# Board_ESP32_V1.net
KiCad netlist of a schematic drawn in EAGLE
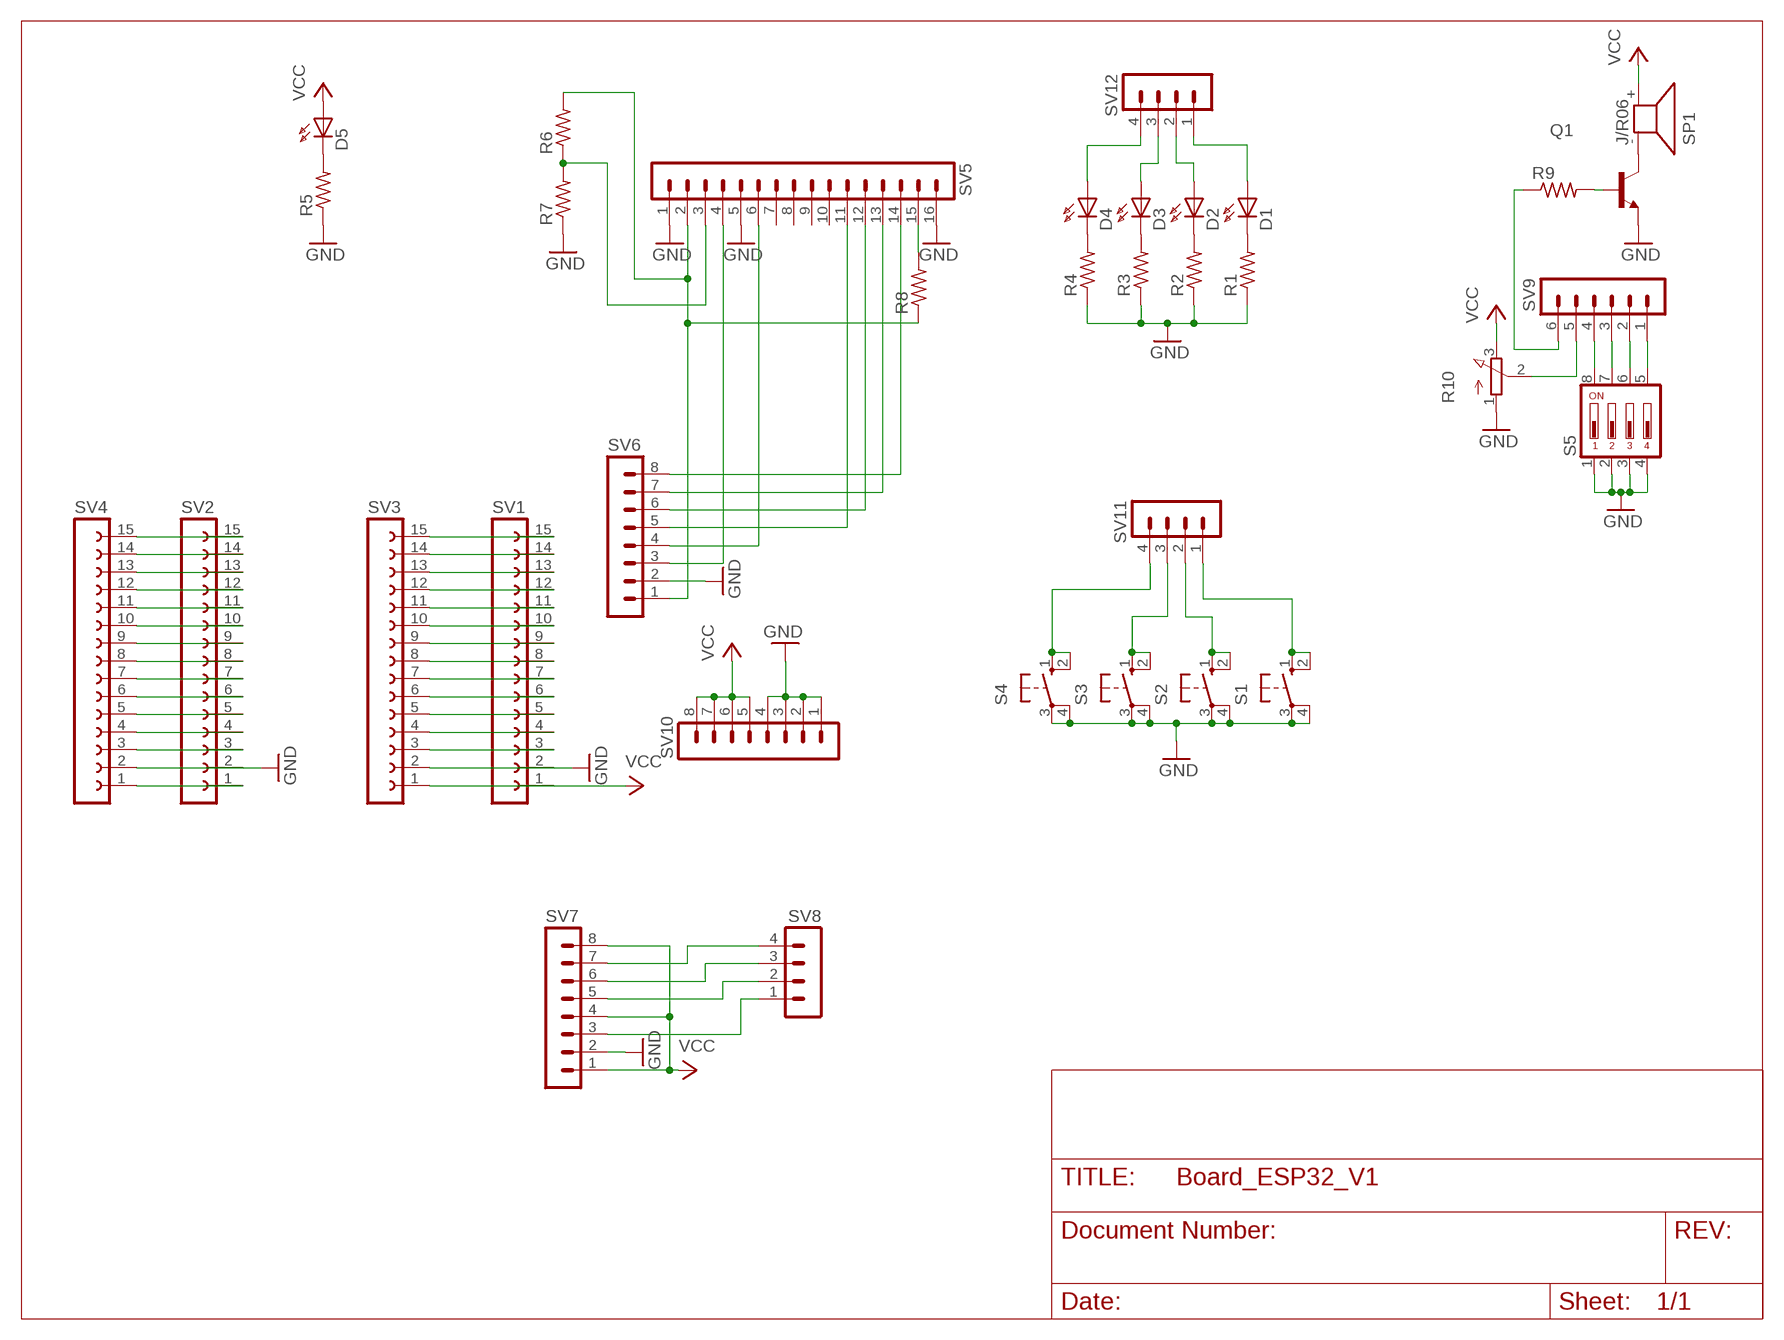
[diagram p0: schematic, sheet 1]

(export (version "E")
  (design (tool "Eeschema 10.0.6"))
  (components
    (comp (ref "D1")
      (value "LED3MM")
      (footprint "eagle-import:LED3MM")
      (libsource (lib "eagle-import") (part "LED3MM"))
    )
    (comp (ref "D2")
      (value "LED3MM")
      (footprint "eagle-import:LED3MM")
      (libsource (lib "eagle-import") (part "LED3MM"))
    )
    (comp (ref "D3")
      (value "LED3MM")
      (footprint "eagle-import:LED3MM")
      (libsource (lib "eagle-import") (part "LED3MM"))
    )
    (comp (ref "D4")
      (value "LED3MM")
      (footprint "eagle-import:LED3MM")
      (libsource (lib "eagle-import") (part "LED3MM"))
    )
    (comp (ref "D5")
      (value "LED3MM")
      (footprint "eagle-import:LED3MM")
      (libsource (lib "eagle-import") (part "LED3MM"))
    )
    (comp (ref "Q1")
      (value "2N3904")
      (footprint "eagle-import:TO92")
      (libsource (lib "eagle-import") (part "2N3904"))
    )
    (comp (ref "R1")
      (value "R-US_0207/10")
      (footprint "eagle-import:0207_10")
      (libsource (lib "eagle-import") (part "R-US_0207/10"))
    )
    (comp (ref "R2")
      (value "R-US_0207/10")
      (footprint "eagle-import:0207_10")
      (libsource (lib "eagle-import") (part "R-US_0207/10"))
    )
    (comp (ref "R3")
      (value "R-US_0207/10")
      (footprint "eagle-import:0207_10")
      (libsource (lib "eagle-import") (part "R-US_0207/10"))
    )
    (comp (ref "R4")
      (value "R-US_0207/10")
      (footprint "eagle-import:0207_10")
      (libsource (lib "eagle-import") (part "R-US_0207/10"))
    )
    (comp (ref "R5")
      (value "R-US_0207/10")
      (footprint "eagle-import:0207_10")
      (libsource (lib "eagle-import") (part "R-US_0207/10"))
    )
    (comp (ref "R6")
      (value "R-US_0207/10")
      (footprint "eagle-import:0207_10")
      (libsource (lib "eagle-import") (part "R-US_0207/10"))
    )
    (comp (ref "R7")
      (value "R-US_0207/10")
      (footprint "eagle-import:0207_10")
      (libsource (lib "eagle-import") (part "R-US_0207/10"))
    )
    (comp (ref "R8")
      (value "R-US_0207/10")
      (footprint "eagle-import:0207_10")
      (libsource (lib "eagle-import") (part "R-US_0207/10"))
    )
    (comp (ref "R9")
      (value "R-US_0207/10")
      (footprint "eagle-import:0207_10")
      (libsource (lib "eagle-import") (part "R-US_0207/10"))
    )
    (comp (ref "R10")
      (value "3RP/1610N")
      (footprint "eagle-import:3RP_1610N")
      (libsource (lib "eagle-import") (part "3RP/1610N"))
    )
    (comp (ref "S1")
      (value "10-XX")
      (footprint "eagle-import:B3F-10XX")
      (fields (field (name "MPN") "B3F-1000"))
      (libsource (lib "eagle-import") (part "10-XX"))
    )
    (comp (ref "S2")
      (value "10-XX")
      (footprint "eagle-import:B3F-10XX")
      (fields (field (name "MPN") "B3F-1000"))
      (libsource (lib "eagle-import") (part "10-XX"))
    )
    (comp (ref "S3")
      (value "10-XX")
      (footprint "eagle-import:B3F-10XX")
      (fields (field (name "MPN") "B3F-1000"))
      (libsource (lib "eagle-import") (part "10-XX"))
    )
    (comp (ref "S4")
      (value "10-XX")
      (footprint "eagle-import:B3F-10XX")
      (fields (field (name "MPN") "B3F-1000"))
      (libsource (lib "eagle-import") (part "10-XX"))
    )
    (comp (ref "S5")
      (value "DIP04YL")
      (footprint "eagle-import:DIP04YL")
      (libsource (lib "eagle-import") (part "DIP04YL"))
    )
    (comp (ref "SP1")
      (value "J/R06")
      (footprint "eagle-import:J_R06")
      (libsource (lib "eagle-import") (part "J/R06"))
    )
    (comp (ref "SV1")
      (value "FE15-1")
      (footprint "eagle-import:FE15")
      (libsource (lib "eagle-import") (part "FE15-1"))
    )
    (comp (ref "SV2")
      (value "FE15-1")
      (footprint "eagle-import:FE15")
      (libsource (lib "eagle-import") (part "FE15-1"))
    )
    (comp (ref "SV3")
      (value "FE15-1")
      (footprint "eagle-import:FE15")
      (libsource (lib "eagle-import") (part "FE15-1"))
    )
    (comp (ref "SV4")
      (value "FE15-1")
      (footprint "eagle-import:FE15")
      (libsource (lib "eagle-import") (part "FE15-1"))
    )
    (comp (ref "SV5")
      (value "MA16-1")
      (footprint "eagle-import:MA16-1")
      (libsource (lib "eagle-import") (part "MA16-1"))
    )
    (comp (ref "SV6")
      (value "MA08-1")
      (footprint "eagle-import:MA08-1")
      (libsource (lib "eagle-import") (part "MA08-1"))
    )
    (comp (ref "SV7")
      (value "MA08-1")
      (footprint "eagle-import:MA08-1")
      (libsource (lib "eagle-import") (part "MA08-1"))
    )
    (comp (ref "SV8")
      (value "MA04-1")
      (footprint "eagle-import:MA04-1")
      (libsource (lib "eagle-import") (part "MA04-1"))
    )
    (comp (ref "SV9")
      (value "MA06-1")
      (footprint "eagle-import:MA06-1")
      (libsource (lib "eagle-import") (part "MA06-1"))
    )
    (comp (ref "SV10")
      (value "MA08-1")
      (footprint "eagle-import:MA08-1")
      (libsource (lib "eagle-import") (part "MA08-1"))
    )
    (comp (ref "SV11")
      (value "MA04-1")
      (footprint "eagle-import:MA04-1")
      (libsource (lib "eagle-import") (part "MA04-1"))
    )
    (comp (ref "SV12")
      (value "MA04-1")
      (footprint "eagle-import:MA04-1")
      (libsource (lib "eagle-import") (part "MA04-1"))
    )
  )
  (nets
    (net (code "1") (name "GND") (class "Default")
      (node (ref "Q1") (pin "3") (pinfunction "E_3") (pintype "passive"))
      (node (ref "R1") (pin "1") (pinfunction "1_1") (pintype "passive"))
      (node (ref "R10") (pin "1") (pinfunction "A_1") (pintype "passive"))
      (node (ref "R2") (pin "1") (pinfunction "1_1") (pintype "passive"))
      (node (ref "R3") (pin "1") (pinfunction "1_1") (pintype "passive"))
      (node (ref "R4") (pin "1") (pinfunction "1_1") (pintype "passive"))
      (node (ref "R5") (pin "1") (pinfunction "1_1") (pintype "passive"))
      (node (ref "R7") (pin "1") (pinfunction "1_1") (pintype "passive"))
      (node (ref "S1") (pin "3") (pinfunction "P_3") (pintype "passive"))
      (node (ref "S1") (pin "4") (pinfunction "P1_4") (pintype "passive"))
      (node (ref "S2") (pin "3") (pinfunction "P_3") (pintype "passive"))
      (node (ref "S2") (pin "4") (pinfunction "P1_4") (pintype "passive"))
      (node (ref "S3") (pin "3") (pinfunction "P_3") (pintype "passive"))
      (node (ref "S3") (pin "4") (pinfunction "P1_4") (pintype "passive"))
      (node (ref "S4") (pin "3") (pinfunction "P_3") (pintype "passive"))
      (node (ref "S4") (pin "4") (pinfunction "P1_4") (pintype "passive"))
      (node (ref "S5") (pin "1") (pinfunction "1_1") (pintype "passive"))
      (node (ref "S5") (pin "2") (pinfunction "2_2") (pintype "passive"))
      (node (ref "S5") (pin "3") (pinfunction "3_3") (pintype "passive"))
      (node (ref "S5") (pin "4") (pinfunction "4_4") (pintype "passive"))
      (node (ref "SV1") (pin "2") (pinfunction "2_2") (pintype "passive"))
      (node (ref "SV10") (pin "1") (pinfunction "1_1") (pintype "passive"))
      (node (ref "SV10") (pin "2") (pinfunction "2_2") (pintype "passive"))
      (node (ref "SV10") (pin "3") (pinfunction "3_3") (pintype "passive"))
      (node (ref "SV10") (pin "4") (pinfunction "4_4") (pintype "passive"))
      (node (ref "SV2") (pin "2") (pinfunction "2_2") (pintype "passive"))
      (node (ref "SV3") (pin "2") (pinfunction "2_2") (pintype "passive"))
      (node (ref "SV4") (pin "2") (pinfunction "2_2") (pintype "passive"))
      (node (ref "SV5") (pin "1") (pinfunction "1_1") (pintype "passive"))
      (node (ref "SV5") (pin "16") (pinfunction "16_16") (pintype "passive"))
      (node (ref "SV5") (pin "5") (pinfunction "5_5") (pintype "passive"))
      (node (ref "SV6") (pin "2") (pinfunction "2_2") (pintype "passive"))
      (node (ref "SV7") (pin "2") (pinfunction "2_2") (pintype "passive"))
    )
    (net (code "2") (name "Net-(D1-C)") (class "Default")
      (node (ref "D1") (pin "K") (pinfunction "C_K") (pintype "passive"))
      (node (ref "R1") (pin "2") (pinfunction "2_2") (pintype "passive"))
    )
    (net (code "3") (name "Net-(D1-PadA)") (class "Default")
      (node (ref "D1") (pin "A") (pinfunction "A_A") (pintype "passive"))
      (node (ref "SV12") (pin "1") (pinfunction "1_1") (pintype "passive"))
    )
    (net (code "4") (name "Net-(D2-C)") (class "Default")
      (node (ref "D2") (pin "K") (pinfunction "C_K") (pintype "passive"))
      (node (ref "R2") (pin "2") (pinfunction "2_2") (pintype "passive"))
    )
    (net (code "5") (name "Net-(D2-PadA)") (class "Default")
      (node (ref "D2") (pin "A") (pinfunction "A_A") (pintype "passive"))
      (node (ref "SV12") (pin "2") (pinfunction "2_2") (pintype "passive"))
    )
    (net (code "6") (name "Net-(D3-C)") (class "Default")
      (node (ref "D3") (pin "K") (pinfunction "C_K") (pintype "passive"))
      (node (ref "R3") (pin "2") (pinfunction "2_2") (pintype "passive"))
    )
    (net (code "7") (name "Net-(D3-PadA)") (class "Default")
      (node (ref "D3") (pin "A") (pinfunction "A_A") (pintype "passive"))
      (node (ref "SV12") (pin "3") (pinfunction "3_3") (pintype "passive"))
    )
    (net (code "8") (name "Net-(D4-C)") (class "Default")
      (node (ref "D4") (pin "K") (pinfunction "C_K") (pintype "passive"))
      (node (ref "R4") (pin "2") (pinfunction "2_2") (pintype "passive"))
    )
    (net (code "9") (name "Net-(D4-PadA)") (class "Default")
      (node (ref "D4") (pin "A") (pinfunction "A_A") (pintype "passive"))
      (node (ref "SV12") (pin "4") (pinfunction "4_4") (pintype "passive"))
    )
    (net (code "10") (name "Net-(D5-C)") (class "Default")
      (node (ref "D5") (pin "K") (pinfunction "C_K") (pintype "passive"))
      (node (ref "R5") (pin "2") (pinfunction "2_2") (pintype "passive"))
    )
    (net (code "11") (name "Net-(Q1-B)") (class "Default")
      (node (ref "Q1") (pin "2") (pinfunction "B_2") (pintype "passive"))
      (node (ref "R9") (pin "2") (pinfunction "2_2") (pintype "passive"))
    )
    (net (code "12") (name "Net-(Q1-C)") (class "Default")
      (node (ref "Q1") (pin "1") (pinfunction "C_1") (pintype "passive"))
      (node (ref "SP1") (pin "-") (pinfunction "1_-") (pintype "passive"))
    )
    (net (code "13") (name "Net-(R6-Pad1)") (class "Default")
      (node (ref "R6") (pin "1") (pinfunction "1_1") (pintype "passive"))
      (node (ref "R7") (pin "2") (pinfunction "2_2") (pintype "passive"))
      (node (ref "SV5") (pin "3") (pinfunction "3_3") (pintype "passive"))
    )
    (net (code "14") (name "Net-(R6-Pad2)") (class "Default")
      (node (ref "R6") (pin "2") (pinfunction "2_2") (pintype "passive"))
      (node (ref "R8") (pin "1") (pinfunction "1_1") (pintype "passive"))
      (node (ref "SV5") (pin "2") (pinfunction "2_2") (pintype "passive"))
      (node (ref "SV6") (pin "1") (pinfunction "1_1") (pintype "passive"))
    )
    (net (code "15") (name "Net-(R8-Pad2)") (class "Default")
      (node (ref "R8") (pin "2") (pinfunction "2_2") (pintype "passive"))
      (node (ref "SV5") (pin "15") (pinfunction "15_15") (pintype "passive"))
    )
    (net (code "16") (name "Net-(R9-Pad1)") (class "Default")
      (node (ref "R9") (pin "1") (pinfunction "1_1") (pintype "passive"))
      (node (ref "SV9") (pin "6") (pinfunction "6_6") (pintype "passive"))
    )
    (net (code "17") (name "Net-(R10-S)") (class "Default")
      (node (ref "R10") (pin "2") (pinfunction "S_2") (pintype "passive"))
      (node (ref "SV9") (pin "5") (pinfunction "5_5") (pintype "passive"))
    )
    (net (code "18") (name "Net-(S1-S)") (class "Default")
      (node (ref "S1") (pin "1") (pinfunction "S_1") (pintype "passive"))
      (node (ref "S1") (pin "2") (pinfunction "S1_2") (pintype "passive"))
      (node (ref "SV11") (pin "1") (pinfunction "1_1") (pintype "passive"))
    )
    (net (code "19") (name "Net-(S2-S)") (class "Default")
      (node (ref "S2") (pin "1") (pinfunction "S_1") (pintype "passive"))
      (node (ref "S2") (pin "2") (pinfunction "S1_2") (pintype "passive"))
      (node (ref "SV11") (pin "2") (pinfunction "2_2") (pintype "passive"))
    )
    (net (code "20") (name "Net-(S3-S)") (class "Default")
      (node (ref "S3") (pin "1") (pinfunction "S_1") (pintype "passive"))
      (node (ref "S3") (pin "2") (pinfunction "S1_2") (pintype "passive"))
      (node (ref "SV11") (pin "3") (pinfunction "3_3") (pintype "passive"))
    )
    (net (code "21") (name "Net-(S4-S)") (class "Default")
      (node (ref "S4") (pin "1") (pinfunction "S_1") (pintype "passive"))
      (node (ref "S4") (pin "2") (pinfunction "S1_2") (pintype "passive"))
      (node (ref "SV11") (pin "4") (pinfunction "4_4") (pintype "passive"))
    )
    (net (code "22") (name "Net-(S5-Pad5)") (class "Default")
      (node (ref "S5") (pin "5") (pinfunction "5_5") (pintype "passive"))
      (node (ref "SV9") (pin "1") (pinfunction "1_1") (pintype "passive"))
    )
    (net (code "23") (name "Net-(S5-Pad6)") (class "Default")
      (node (ref "S5") (pin "6") (pinfunction "6_6") (pintype "passive"))
      (node (ref "SV9") (pin "2") (pinfunction "2_2") (pintype "passive"))
    )
    (net (code "24") (name "Net-(S5-Pad7)") (class "Default")
      (node (ref "S5") (pin "7") (pinfunction "7_7") (pintype "passive"))
      (node (ref "SV9") (pin "3") (pinfunction "3_3") (pintype "passive"))
    )
    (net (code "25") (name "Net-(S5-Pad8)") (class "Default")
      (node (ref "S5") (pin "8") (pinfunction "8_8") (pintype "passive"))
      (node (ref "SV9") (pin "4") (pinfunction "4_4") (pintype "passive"))
    )
    (net (code "26") (name "Net-(SV1-Pad3)") (class "Default")
      (node (ref "SV1") (pin "3") (pinfunction "3_3") (pintype "passive"))
      (node (ref "SV3") (pin "3") (pinfunction "3_3") (pintype "passive"))
    )
    (net (code "27") (name "Net-(SV1-Pad4)") (class "Default")
      (node (ref "SV1") (pin "4") (pinfunction "4_4") (pintype "passive"))
      (node (ref "SV3") (pin "4") (pinfunction "4_4") (pintype "passive"))
    )
    (net (code "28") (name "Net-(SV1-Pad5)") (class "Default")
      (node (ref "SV1") (pin "5") (pinfunction "5_5") (pintype "passive"))
      (node (ref "SV3") (pin "5") (pinfunction "5_5") (pintype "passive"))
    )
    (net (code "29") (name "Net-(SV1-Pad6)") (class "Default")
      (node (ref "SV1") (pin "6") (pinfunction "6_6") (pintype "passive"))
      (node (ref "SV3") (pin "6") (pinfunction "6_6") (pintype "passive"))
    )
    (net (code "30") (name "Net-(SV1-Pad7)") (class "Default")
      (node (ref "SV1") (pin "7") (pinfunction "7_7") (pintype "passive"))
      (node (ref "SV3") (pin "7") (pinfunction "7_7") (pintype "passive"))
    )
    (net (code "31") (name "Net-(SV1-Pad8)") (class "Default")
      (node (ref "SV1") (pin "8") (pinfunction "8_8") (pintype "passive"))
      (node (ref "SV3") (pin "8") (pinfunction "8_8") (pintype "passive"))
    )
    (net (code "32") (name "Net-(SV1-Pad9)") (class "Default")
      (node (ref "SV1") (pin "9") (pinfunction "9_9") (pintype "passive"))
      (node (ref "SV3") (pin "9") (pinfunction "9_9") (pintype "passive"))
    )
    (net (code "33") (name "Net-(SV1-Pad10)") (class "Default")
      (node (ref "SV1") (pin "10") (pinfunction "10_10") (pintype "passive"))
      (node (ref "SV3") (pin "10") (pinfunction "10_10") (pintype "passive"))
    )
    (net (code "34") (name "Net-(SV1-Pad11)") (class "Default")
      (node (ref "SV1") (pin "11") (pinfunction "11_11") (pintype "passive"))
      (node (ref "SV3") (pin "11") (pinfunction "11_11") (pintype "passive"))
    )
    (net (code "35") (name "Net-(SV1-Pad12)") (class "Default")
      (node (ref "SV1") (pin "12") (pinfunction "12_12") (pintype "passive"))
      (node (ref "SV3") (pin "12") (pinfunction "12_12") (pintype "passive"))
    )
    (net (code "36") (name "Net-(SV1-Pad13)") (class "Default")
      (node (ref "SV1") (pin "13") (pinfunction "13_13") (pintype "passive"))
      (node (ref "SV3") (pin "13") (pinfunction "13_13") (pintype "passive"))
    )
    (net (code "37") (name "Net-(SV1-Pad14)") (class "Default")
      (node (ref "SV1") (pin "14") (pinfunction "14_14") (pintype "passive"))
      (node (ref "SV3") (pin "14") (pinfunction "14_14") (pintype "passive"))
    )
    (net (code "38") (name "Net-(SV1-Pad15)") (class "Default")
      (node (ref "SV1") (pin "15") (pinfunction "15_15") (pintype "passive"))
      (node (ref "SV3") (pin "15") (pinfunction "15_15") (pintype "passive"))
    )
    (net (code "39") (name "Net-(SV2-Pad1)") (class "Default")
      (node (ref "SV2") (pin "1") (pinfunction "1_1") (pintype "passive"))
      (node (ref "SV4") (pin "1") (pinfunction "1_1") (pintype "passive"))
    )
    (net (code "40") (name "Net-(SV2-Pad3)") (class "Default")
      (node (ref "SV2") (pin "3") (pinfunction "3_3") (pintype "passive"))
      (node (ref "SV4") (pin "3") (pinfunction "3_3") (pintype "passive"))
    )
    (net (code "41") (name "Net-(SV2-Pad4)") (class "Default")
      (node (ref "SV2") (pin "4") (pinfunction "4_4") (pintype "passive"))
      (node (ref "SV4") (pin "4") (pinfunction "4_4") (pintype "passive"))
    )
    (net (code "42") (name "Net-(SV2-Pad5)") (class "Default")
      (node (ref "SV2") (pin "5") (pinfunction "5_5") (pintype "passive"))
      (node (ref "SV4") (pin "5") (pinfunction "5_5") (pintype "passive"))
    )
    (net (code "43") (name "Net-(SV2-Pad6)") (class "Default")
      (node (ref "SV2") (pin "6") (pinfunction "6_6") (pintype "passive"))
      (node (ref "SV4") (pin "6") (pinfunction "6_6") (pintype "passive"))
    )
    (net (code "44") (name "Net-(SV2-Pad7)") (class "Default")
      (node (ref "SV2") (pin "7") (pinfunction "7_7") (pintype "passive"))
      (node (ref "SV4") (pin "7") (pinfunction "7_7") (pintype "passive"))
    )
    (net (code "45") (name "Net-(SV2-Pad8)") (class "Default")
      (node (ref "SV2") (pin "8") (pinfunction "8_8") (pintype "passive"))
      (node (ref "SV4") (pin "8") (pinfunction "8_8") (pintype "passive"))
    )
    (net (code "46") (name "Net-(SV2-Pad9)") (class "Default")
      (node (ref "SV2") (pin "9") (pinfunction "9_9") (pintype "passive"))
      (node (ref "SV4") (pin "9") (pinfunction "9_9") (pintype "passive"))
    )
    (net (code "47") (name "Net-(SV2-Pad10)") (class "Default")
      (node (ref "SV2") (pin "10") (pinfunction "10_10") (pintype "passive"))
      (node (ref "SV4") (pin "10") (pinfunction "10_10") (pintype "passive"))
    )
    (net (code "48") (name "Net-(SV2-Pad11)") (class "Default")
      (node (ref "SV2") (pin "11") (pinfunction "11_11") (pintype "passive"))
      (node (ref "SV4") (pin "11") (pinfunction "11_11") (pintype "passive"))
    )
    (net (code "49") (name "Net-(SV2-Pad12)") (class "Default")
      (node (ref "SV2") (pin "12") (pinfunction "12_12") (pintype "passive"))
      (node (ref "SV4") (pin "12") (pinfunction "12_12") (pintype "passive"))
    )
    (net (code "50") (name "Net-(SV2-Pad13)") (class "Default")
      (node (ref "SV2") (pin "13") (pinfunction "13_13") (pintype "passive"))
      (node (ref "SV4") (pin "13") (pinfunction "13_13") (pintype "passive"))
    )
    (net (code "51") (name "Net-(SV2-Pad14)") (class "Default")
      (node (ref "SV2") (pin "14") (pinfunction "14_14") (pintype "passive"))
      (node (ref "SV4") (pin "14") (pinfunction "14_14") (pintype "passive"))
    )
    (net (code "52") (name "Net-(SV2-Pad15)") (class "Default")
      (node (ref "SV2") (pin "15") (pinfunction "15_15") (pintype "passive"))
      (node (ref "SV4") (pin "15") (pinfunction "15_15") (pintype "passive"))
    )
    (net (code "53") (name "Net-(SV5-Pad4)") (class "Default")
      (node (ref "SV5") (pin "4") (pinfunction "4_4") (pintype "passive"))
      (node (ref "SV6") (pin "3") (pinfunction "3_3") (pintype "passive"))
    )
    (net (code "54") (name "Net-(SV5-Pad6)") (class "Default")
      (node (ref "SV5") (pin "6") (pinfunction "6_6") (pintype "passive"))
      (node (ref "SV6") (pin "4") (pinfunction "4_4") (pintype "passive"))
    )
    (net (code "55") (name "Net-(SV5-Pad11)") (class "Default")
      (node (ref "SV5") (pin "11") (pinfunction "11_11") (pintype "passive"))
      (node (ref "SV6") (pin "5") (pinfunction "5_5") (pintype "passive"))
    )
    (net (code "56") (name "Net-(SV5-Pad12)") (class "Default")
      (node (ref "SV5") (pin "12") (pinfunction "12_12") (pintype "passive"))
      (node (ref "SV6") (pin "6") (pinfunction "6_6") (pintype "passive"))
    )
    (net (code "57") (name "Net-(SV5-Pad13)") (class "Default")
      (node (ref "SV5") (pin "13") (pinfunction "13_13") (pintype "passive"))
      (node (ref "SV6") (pin "7") (pinfunction "7_7") (pintype "passive"))
    )
    (net (code "58") (name "Net-(SV5-Pad14)") (class "Default")
      (node (ref "SV5") (pin "14") (pinfunction "14_14") (pintype "passive"))
      (node (ref "SV6") (pin "8") (pinfunction "8_8") (pintype "passive"))
    )
    (net (code "59") (name "Net-(SV7-Pad3)") (class "Default")
      (node (ref "SV7") (pin "3") (pinfunction "3_3") (pintype "passive"))
      (node (ref "SV8") (pin "1") (pinfunction "1_1") (pintype "passive"))
    )
    (net (code "60") (name "Net-(SV7-Pad5)") (class "Default")
      (node (ref "SV7") (pin "5") (pinfunction "5_5") (pintype "passive"))
      (node (ref "SV8") (pin "2") (pinfunction "2_2") (pintype "passive"))
    )
    (net (code "61") (name "Net-(SV7-Pad6)") (class "Default")
      (node (ref "SV7") (pin "6") (pinfunction "6_6") (pintype "passive"))
      (node (ref "SV8") (pin "3") (pinfunction "3_3") (pintype "passive"))
    )
    (net (code "62") (name "Net-(SV7-Pad7)") (class "Default")
      (node (ref "SV7") (pin "7") (pinfunction "7_7") (pintype "passive"))
      (node (ref "SV8") (pin "4") (pinfunction "4_4") (pintype "passive"))
    )
    (net (code "63") (name "VCC") (class "Default")
      (node (ref "D5") (pin "A") (pinfunction "A_A") (pintype "passive"))
      (node (ref "R10") (pin "3") (pinfunction "E_3") (pintype "passive"))
      (node (ref "SP1") (pin "+") (pinfunction "2_+") (pintype "passive"))
      (node (ref "SV1") (pin "1") (pinfunction "1_1") (pintype "passive"))
      (node (ref "SV10") (pin "5") (pinfunction "5_5") (pintype "passive"))
      (node (ref "SV10") (pin "6") (pinfunction "6_6") (pintype "passive"))
      (node (ref "SV10") (pin "7") (pinfunction "7_7") (pintype "passive"))
      (node (ref "SV10") (pin "8") (pinfunction "8_8") (pintype "passive"))
      (node (ref "SV3") (pin "1") (pinfunction "1_1") (pintype "passive"))
      (node (ref "SV7") (pin "1") (pinfunction "1_1") (pintype "passive"))
      (node (ref "SV7") (pin "4") (pinfunction "4_4") (pintype "passive"))
      (node (ref "SV7") (pin "8") (pinfunction "8_8") (pintype "passive"))
    )
    (net (code "64") (name "unconnected-(SV5-Pad7)") (class "Default")
      (node (ref "SV5") (pin "7") (pinfunction "7_7") (pintype "passive"))
    )
    (net (code "65") (name "unconnected-(SV5-Pad8)") (class "Default")
      (node (ref "SV5") (pin "8") (pinfunction "8_8") (pintype "passive"))
    )
    (net (code "66") (name "unconnected-(SV5-Pad9)") (class "Default")
      (node (ref "SV5") (pin "9") (pinfunction "9_9") (pintype "passive"))
    )
    (net (code "67") (name "unconnected-(SV5-Pad10)") (class "Default")
      (node (ref "SV5") (pin "10") (pinfunction "10_10") (pintype "passive"))
    )
  )
)
